# FeatherWing_for_Grove.net
KiCad netlist of a schematic drawn in EAGLE
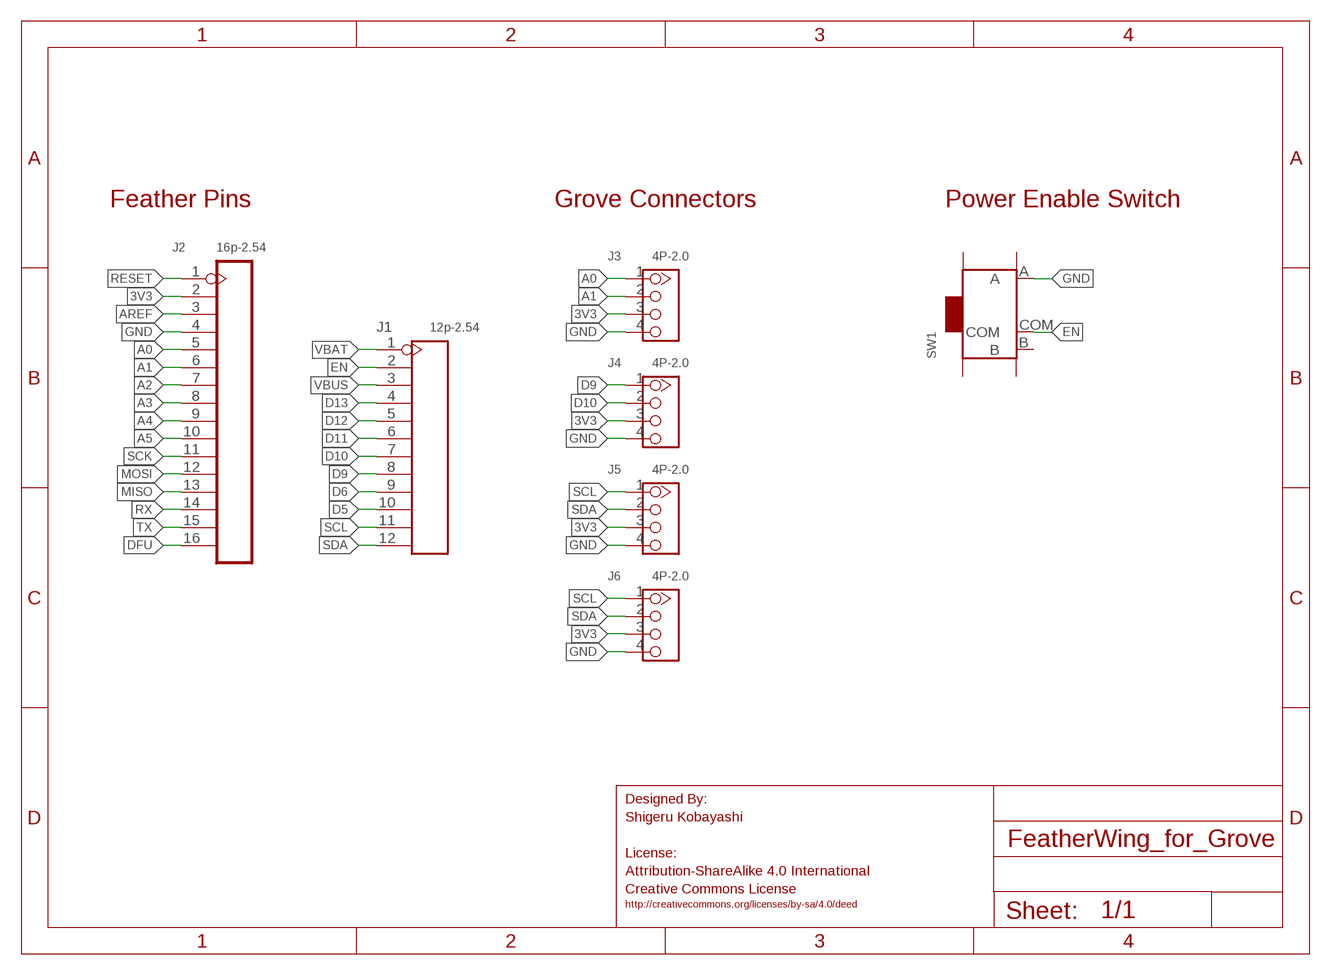
[diagram p0: schematic, sheet 1]

(export (version "E")
  (design (tool "Eeschema 10.0.6"))
  (components
    (comp (ref "J1")
      (value "12p-2.54")
      (footprint "eagle-import:H12-2.54")
      (fields (field (name "MPN") "P125-1112A0BS116AX"))
      (libsource (lib "eagle-import") (part "DIP-BLACK-MALE-HEADER(12P-2.54)"))
    )
    (comp (ref "J2")
      (value "16p-2.54")
      (footprint "eagle-import:H16-2.54")
      (fields (field (name "MPN") "P125-1116A0BS116AX"))
      (libsource (lib "eagle-import") (part "DIP-BLACK-MALE-HEADER-VERT(16P-2.54)"))
    )
    (comp (ref "J3")
      (value "4P-2.0")
      (footprint "eagle-import:HW4-2.0")
      (libsource (lib "eagle-import") (part "GROVE-CONNECTOR-DIP(4P-2.0)"))
    )
    (comp (ref "J4")
      (value "4P-2.0")
      (footprint "eagle-import:HW4-2.0")
      (libsource (lib "eagle-import") (part "GROVE-CONNECTOR-DIP(4P-2.0)"))
    )
    (comp (ref "J5")
      (value "4P-2.0")
      (footprint "eagle-import:HW4-2.0")
      (libsource (lib "eagle-import") (part "GROVE-CONNECTOR-DIP(4P-2.0)"))
    )
    (comp (ref "J6")
      (value "4P-2.0")
      (footprint "eagle-import:HW4-2.0")
      (libsource (lib "eagle-import") (part "GROVE-CONNECTOR-DIP(4P-2.0)"))
    )
    (comp (ref "SW1")
      (value "SMD-TOGGLE-SWITCH-ON-ON(3+4P-6.7X2.7MM)")
      (footprint "eagle-import:SW7-SMD-L6.7X2.7X3.2MM")
      (libsource (lib "eagle-import") (part "SMD-TOGGLE-SWITCH-ON-ON(3+4P-6.7X2.7MM)"))
    )
  )
  (nets
    (net (code "1") (name "3V3") (class "Default")
      (node (ref "J2") (pin "2") (pinfunction "2_2") (pintype "passive"))
      (node (ref "J3") (pin "3") (pinfunction "3_3") (pintype "bidirectional"))
      (node (ref "J4") (pin "3") (pinfunction "3_3") (pintype "bidirectional"))
      (node (ref "J5") (pin "3") (pinfunction "3_3") (pintype "bidirectional"))
      (node (ref "J6") (pin "3") (pinfunction "3_3") (pintype "bidirectional"))
    )
    (net (code "2") (name "A0") (class "Default")
      (node (ref "J2") (pin "5") (pinfunction "5_5") (pintype "passive"))
      (node (ref "J3") (pin "1") (pinfunction "1_1") (pintype "bidirectional"))
    )
    (net (code "3") (name "A1") (class "Default")
      (node (ref "J2") (pin "6") (pinfunction "6_6") (pintype "passive"))
      (node (ref "J3") (pin "2") (pinfunction "2_2") (pintype "bidirectional"))
    )
    (net (code "4") (name "A2") (class "Default")
      (node (ref "J2") (pin "7") (pinfunction "7_7") (pintype "passive"))
    )
    (net (code "5") (name "A3") (class "Default")
      (node (ref "J2") (pin "8") (pinfunction "8_8") (pintype "passive"))
    )
    (net (code "6") (name "A4") (class "Default")
      (node (ref "J2") (pin "9") (pinfunction "9_9") (pintype "passive"))
    )
    (net (code "7") (name "A5") (class "Default")
      (node (ref "J2") (pin "10") (pinfunction "10_10") (pintype "passive"))
    )
    (net (code "8") (name "AREF") (class "Default")
      (node (ref "J2") (pin "3") (pinfunction "3_3") (pintype "passive"))
    )
    (net (code "9") (name "D5") (class "Default")
      (node (ref "J1") (pin "10") (pinfunction "10_10") (pintype "bidirectional"))
    )
    (net (code "10") (name "D6") (class "Default")
      (node (ref "J1") (pin "9") (pinfunction "9_9") (pintype "bidirectional"))
    )
    (net (code "11") (name "D9") (class "Default")
      (node (ref "J1") (pin "8") (pinfunction "8_8") (pintype "bidirectional"))
      (node (ref "J4") (pin "1") (pinfunction "1_1") (pintype "bidirectional"))
    )
    (net (code "12") (name "D10") (class "Default")
      (node (ref "J1") (pin "7") (pinfunction "7_7") (pintype "bidirectional"))
      (node (ref "J4") (pin "2") (pinfunction "2_2") (pintype "bidirectional"))
    )
    (net (code "13") (name "D11") (class "Default")
      (node (ref "J1") (pin "6") (pinfunction "6_6") (pintype "bidirectional"))
    )
    (net (code "14") (name "D12") (class "Default")
      (node (ref "J1") (pin "5") (pinfunction "5_5") (pintype "bidirectional"))
    )
    (net (code "15") (name "D13") (class "Default")
      (node (ref "J1") (pin "4") (pinfunction "4_4") (pintype "bidirectional"))
    )
    (net (code "16") (name "DFU") (class "Default")
      (node (ref "J2") (pin "16") (pinfunction "16_16") (pintype "passive"))
    )
    (net (code "17") (name "EN") (class "Default")
      (node (ref "J1") (pin "2") (pinfunction "2_2") (pintype "bidirectional"))
      (node (ref "SW1") (pin "COM") (pinfunction "COM_COM") (pintype "bidirectional"))
    )
    (net (code "18") (name "GND") (class "Default")
      (node (ref "J2") (pin "4") (pinfunction "4_4") (pintype "passive"))
      (node (ref "J3") (pin "4") (pinfunction "4_4") (pintype "bidirectional"))
      (node (ref "J4") (pin "4") (pinfunction "4_4") (pintype "bidirectional"))
      (node (ref "J5") (pin "4") (pinfunction "4_4") (pintype "bidirectional"))
      (node (ref "J6") (pin "4") (pinfunction "4_4") (pintype "bidirectional"))
      (node (ref "SW1") (pin "A") (pinfunction "A_A") (pintype "bidirectional"))
    )
    (net (code "19") (name "MISO") (class "Default")
      (node (ref "J2") (pin "13") (pinfunction "13_13") (pintype "passive"))
    )
    (net (code "20") (name "MOSI") (class "Default")
      (node (ref "J2") (pin "12") (pinfunction "12_12") (pintype "passive"))
    )
    (net (code "21") (name "RESET") (class "Default")
      (node (ref "J2") (pin "1") (pinfunction "1_1") (pintype "passive"))
    )
    (net (code "22") (name "RX") (class "Default")
      (node (ref "J2") (pin "14") (pinfunction "14_14") (pintype "passive"))
    )
    (net (code "23") (name "SCK") (class "Default")
      (node (ref "J2") (pin "11") (pinfunction "11_11") (pintype "passive"))
    )
    (net (code "24") (name "SCL") (class "Default")
      (node (ref "J1") (pin "11") (pinfunction "11_11") (pintype "bidirectional"))
      (node (ref "J5") (pin "1") (pinfunction "1_1") (pintype "bidirectional"))
      (node (ref "J6") (pin "1") (pinfunction "1_1") (pintype "bidirectional"))
    )
    (net (code "25") (name "SDA") (class "Default")
      (node (ref "J1") (pin "12") (pinfunction "12_12") (pintype "bidirectional"))
      (node (ref "J5") (pin "2") (pinfunction "2_2") (pintype "bidirectional"))
      (node (ref "J6") (pin "2") (pinfunction "2_2") (pintype "bidirectional"))
    )
    (net (code "26") (name "TX") (class "Default")
      (node (ref "J2") (pin "15") (pinfunction "15_15") (pintype "passive"))
    )
    (net (code "27") (name "VBAT") (class "Default")
      (node (ref "J1") (pin "1") (pinfunction "1_1") (pintype "bidirectional"))
    )
    (net (code "28") (name "VBUS") (class "Default")
      (node (ref "J1") (pin "3") (pinfunction "3_3") (pintype "bidirectional"))
    )
    (net (code "29") (name "unconnected-(SW1-PadB)") (class "Default")
      (node (ref "SW1") (pin "B") (pinfunction "B_B") (pintype "bidirectional"))
    )
    (net (code "30") (name "unconnected-(SW1-PadSS1)") (class "Default")
      (node (ref "SW1") (pin "SS1") (pinfunction "SS1_SS1") (pintype "bidirectional"))
    )
    (net (code "31") (name "unconnected-(SW1-PadSS2)") (class "Default")
      (node (ref "SW1") (pin "SS2") (pinfunction "SS2_SS2") (pintype "bidirectional"))
    )
    (net (code "32") (name "unconnected-(SW1-PadSS3)") (class "Default")
      (node (ref "SW1") (pin "SS3") (pinfunction "SS3_SS3") (pintype "bidirectional"))
    )
    (net (code "33") (name "unconnected-(SW1-PadSS4)") (class "Default")
      (node (ref "SW1") (pin "SS4") (pinfunction "SS4_SS4") (pintype "bidirectional"))
    )
  )
)
